# nrf51822_dev_dongle_interfaces.net
KiCad netlist of a schematic drawn in Altium Designer
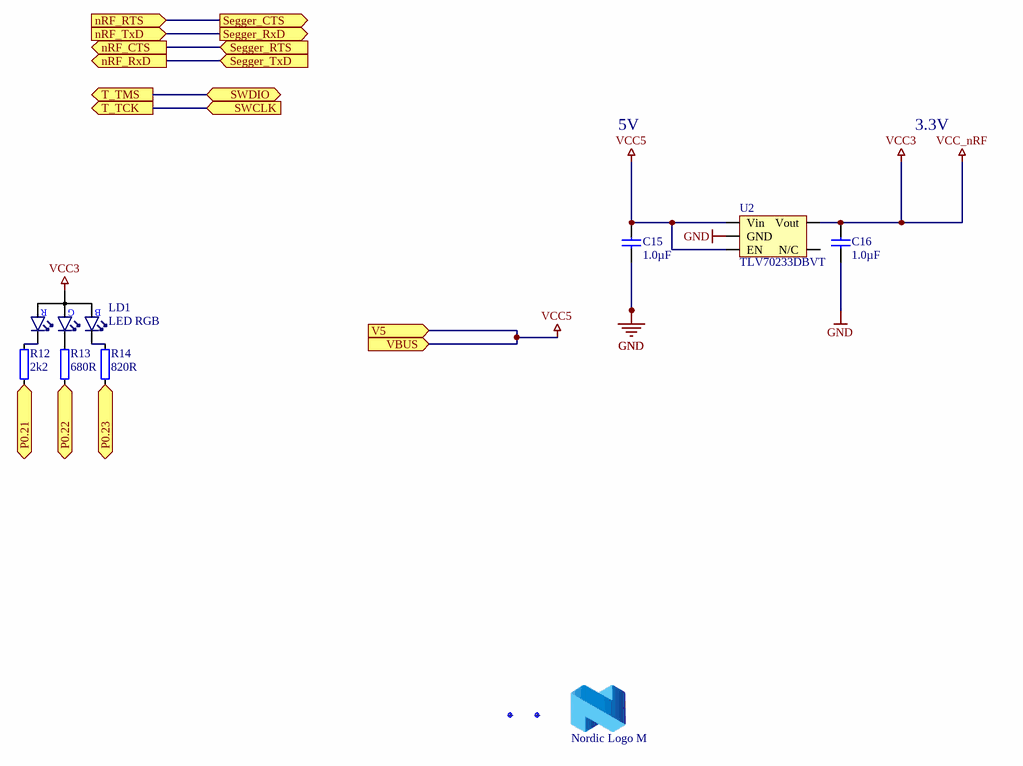
[diagram p0: nrf51822_dev_dongle_interfaces.SchDoc]

(export (version "E")
  (design (tool "Eeschema 10.0.6"))
  (components
    (comp (ref "C15")
      (value "1.0µF")
      (footprint "CAPC1608X06L")
      (description "Capacitor, X5R, ±10%")
      (fields (field (name "PART NUMBER") "C0603-1µ0") (field (name "PUBLISHER") "Nordic Semiconductor"))
      (libsource (lib "Nordic Passive DB") (part "CAP"))
    )
    (comp (ref "C16")
      (value "1.0µF")
      (footprint "CAPC1608X06L")
      (description "Capacitor, X5R, ±10%")
      (fields (field (name "PART NUMBER") "C0603-1µ0") (field (name "PUBLISHER") "Nordic Semiconductor"))
      (libsource (lib "Nordic Passive DB") (part "CAP"))
    )
    (comp (ref "Fid1")
      (value "Fiducial mark")
      (footprint "Fiducial")
      (description "Fiducial Mark")
      (fields (field (name "PART NUMBER") "Fid-Mark") (field (name "PUBLISHER") "Nordic Semiconductor"))
      (libsource (lib "Nordic Passive DB") (part "Fiducial"))
    )
    (comp (ref "Fid2")
      (value "Fiducial mark")
      (footprint "Fiducial")
      (description "Fiducial Mark")
      (fields (field (name "PART NUMBER") "Fid-Mark") (field (name "PUBLISHER") "Nordic Semiconductor"))
      (libsource (lib "Nordic Passive DB") (part "Fiducial"))
    )
    (comp (ref "LD1")
      (value "LED RGB")
      (footprint "SML-LX0404SIUPGUSB")
      (description "RGB LED 1.00 mm x 1.00 mm SMD")
      (fields
        (field (name "PART NUMBER") "SML-LX0404SIUPGUSB")
        (field (name "MANUFACTURER") "Lumex")
        (field (name "PUBLISHER") "Nordic Semiconductor")
      )
      (libsource (lib "Nordic Discrete DB") (part "D{colon}LED_RGB"))
    )
    (comp (ref "LOGO1")
      (value "Nordic Logo M")
      (footprint "NORDIC_LOGO_M")
      (description "Nordic Logo, medium size")
      (fields (field (name "PUBLISHER") "Nordic Semiconductor"))
      (libsource (lib "Nordic Passive DB") (part "Nordic Logo"))
    )
    (comp (ref "R12")
      (value "2k2")
      (footprint "RESC1005X04L")
      (description "Resistor, ±1%, 0.063W")
      (fields (field (name "PART NUMBER") "R0402-2k2") (field (name "PUBLISHER") "Nordic Semiconductor"))
      (libsource (lib "Nordic Passive DB") (part "RES_1"))
    )
    (comp (ref "R13")
      (value "680R")
      (footprint "RESC1005X04L")
      (description "Resistor, ±1%, 0.063W")
      (fields (field (name "PART NUMBER") "R0402-680") (field (name "PUBLISHER") "Nordic Semiconductor"))
      (libsource (lib "Nordic Passive DB") (part "RES_1"))
    )
    (comp (ref "R14")
      (value "820R")
      (footprint "RESC1005X04L")
      (description "Resistor, ±1%, 0.063W")
      (fields (field (name "PART NUMBER") "R0402-820") (field (name "PUBLISHER") "Nordic Semiconductor"))
      (libsource (lib "Nordic Passive DB") (part "RES_1"))
    )
    (comp (ref "U2")
      (value "TLV70233DBVT")
      (footprint "SOT-23-5")
      (description "IC REG LDO 3.3V 300MA SOT23-5")
      (fields
        (field (name "MANUFACTURER") "Texas Instruments")
        (field (name "PUBLISHER") "Nordic Semiconductor")
      )
      (libsource (lib "Nordic Active DB") (part "TLV702xxDBV"))
    )
  )
  (nets
    (net (code "1") (name "/P0.21") (class "Default")
      (node (ref "R12") (pin "1") (pinfunction "1_1") (pintype "passive"))
    )
    (net (code "2") (name "/P0.22") (class "Default")
      (node (ref "R13") (pin "1") (pinfunction "1_1") (pintype "passive"))
    )
    (net (code "3") (name "/P0.23") (class "Default")
      (node (ref "R14") (pin "1") (pinfunction "1_1") (pintype "passive"))
    )
    (net (code "10") (name "GND") (class "Default")
      (node (ref "C15") (pin "1") (pinfunction "1_1") (pintype "passive"))
      (node (ref "C16") (pin "1") (pinfunction "1_1") (pintype "passive"))
      (node (ref "U2") (pin "2") (pinfunction "GND_2") (pintype "passive"))
    )
    (net (code "11") (name "Net-(LD1-C_BLUE)") (class "Default")
      (node (ref "LD1") (pin "3") (pinfunction "C_BLUE_3") (pintype "passive"))
      (node (ref "R14") (pin "2") (pinfunction "2_2") (pintype "passive"))
    )
    (net (code "12") (name "Net-(LD1-C_GREEN)") (class "Default")
      (node (ref "LD1") (pin "2") (pinfunction "C_GREEN_2") (pintype "passive"))
      (node (ref "R13") (pin "2") (pinfunction "2_2") (pintype "passive"))
    )
    (net (code "13") (name "Net-(LD1-C_RED)") (class "Default")
      (node (ref "LD1") (pin "1") (pinfunction "C_RED_1") (pintype "passive"))
      (node (ref "R12") (pin "2") (pinfunction "2_2") (pintype "passive"))
    )
    (net (code "14") (name "VCC3") (class "Default")
      (node (ref "C16") (pin "2") (pinfunction "2_2") (pintype "passive"))
      (node (ref "LD1") (pin "4") (pinfunction "A_4") (pintype "passive"))
      (node (ref "U2") (pin "5") (pinfunction "Vout_5") (pintype "passive"))
    )
    (net (code "15") (name "VCC5") (class "Default")
      (node (ref "C15") (pin "2") (pinfunction "2_2") (pintype "passive"))
      (node (ref "U2") (pin "1") (pinfunction "Vin_1") (pintype "passive"))
      (node (ref "U2") (pin "3") (pinfunction "EN_3") (pintype "passive"))
    )
    (net (code "16") (name "unconnected-(U2-N{slash}C-Pad4)") (class "Default")
      (node (ref "U2") (pin "4") (pinfunction "N/C_4") (pintype "passive"))
    )
  )
)
